# harp_behavior_encoder_v1_2.net
KiCad netlist of a schematic drawn in EAGLE
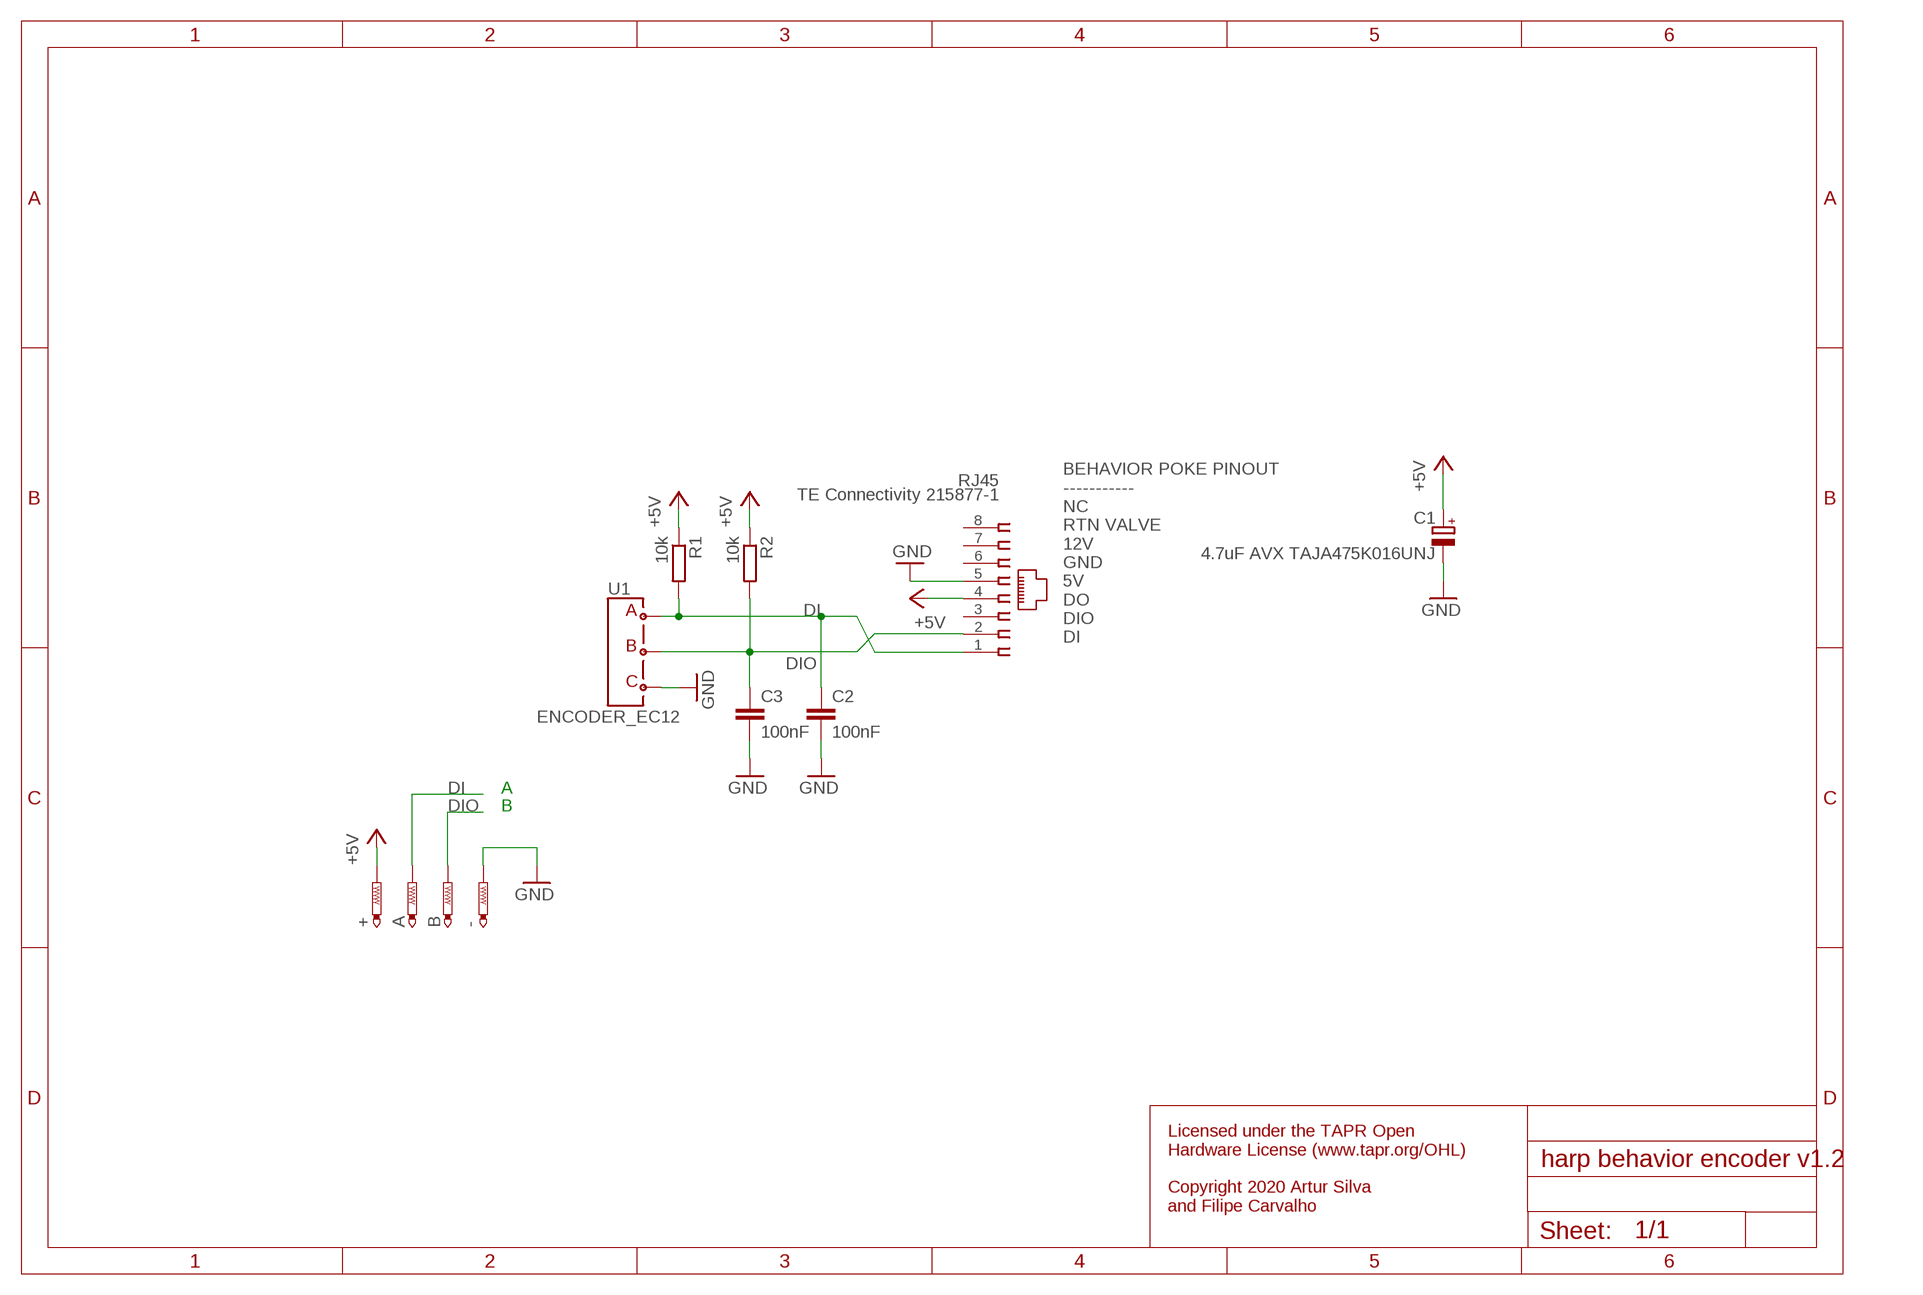
[diagram p0: schematic, sheet 1]

(export (version "E")
  (design (tool "Eeschema 10.0.6"))
  (components
    (comp (ref "+")
      (value "PTR1PAD1-13")
      (footprint "eagle-import:P1-13")
      (libsource (lib "eagle-import") (part "PTR1PAD1-13"))
    )
    (comp (ref "-")
      (value "PTR1PAD1-13")
      (footprint "eagle-import:P1-13")
      (libsource (lib "eagle-import") (part "PTR1PAD1-13"))
    )
    (comp (ref "A")
      (value "PTR1PAD1-13")
      (footprint "eagle-import:P1-13")
      (libsource (lib "eagle-import") (part "PTR1PAD1-13"))
    )
    (comp (ref "B")
      (value "PTR1PAD1-13")
      (footprint "eagle-import:P1-13")
      (libsource (lib "eagle-import") (part "PTR1PAD1-13"))
    )
    (comp (ref "C1")
      (value "4.7uF AVX TAJA475K016UNJ")
      (footprint "eagle-import:A_3216-18W")
      (libsource (lib "eagle-import") (part "CPOL-EUA/3216-18W"))
    )
    (comp (ref "C2")
      (value "100nF")
      (footprint "eagle-import:C0402")
      (libsource (lib "eagle-import") (part "C-EUC0402"))
    )
    (comp (ref "C3")
      (value "100nF")
      (footprint "eagle-import:C0402")
      (libsource (lib "eagle-import") (part "C-EUC0402"))
    )
    (comp (ref "R1")
      (value "10k")
      (footprint "eagle-import:R0402")
      (libsource (lib "eagle-import") (part "R-EU_R0402"))
    )
    (comp (ref "R2")
      (value "10k")
      (footprint "eagle-import:R0402")
      (libsource (lib "eagle-import") (part "R-EU_R0402"))
    )
    (comp (ref "RJ45")
      (value "TE Connectivity 215877-1")
      (footprint "eagle-import:520426-4")
      (libsource (lib "eagle-import") (part "520426-4"))
    )
    (comp (ref "U1")
      (value "ENCODER_EC12")
      (footprint "eagle-import:ENCODER_EC12")
      (libsource (lib "eagle-import") (part "ENCODER_EC12"))
    )
  )
  (nets
    (net (code "1") (name "+5V") (class "Default")
      (node (ref "+") (pin "TP") (pinfunction "TP_TP") (pintype "input"))
      (node (ref "C1") (pin "+") (pinfunction "+_+") (pintype "passive"))
      (node (ref "R1") (pin "1") (pinfunction "1_1") (pintype "passive"))
      (node (ref "R2") (pin "1") (pinfunction "1_1") (pintype "passive"))
      (node (ref "RJ45") (pin "4") (pinfunction "4_4") (pintype "passive"))
    )
    (net (code "2") (name "/DI") (class "Default")
      (node (ref "A") (pin "TP") (pinfunction "TP_TP") (pintype "input"))
      (node (ref "C2") (pin "1") (pinfunction "1_1") (pintype "passive"))
      (node (ref "R1") (pin "2") (pinfunction "2_2") (pintype "passive"))
      (node (ref "RJ45") (pin "1") (pinfunction "1_1") (pintype "passive"))
      (node (ref "U1") (pin "A") (pinfunction "A_A") (pintype "bidirectional"))
    )
    (net (code "3") (name "/DIO") (class "Default")
      (node (ref "B") (pin "TP") (pinfunction "TP_TP") (pintype "input"))
      (node (ref "C3") (pin "1") (pinfunction "1_1") (pintype "passive"))
      (node (ref "R2") (pin "2") (pinfunction "2_2") (pintype "passive"))
      (node (ref "RJ45") (pin "2") (pinfunction "2_2") (pintype "passive"))
      (node (ref "U1") (pin "B") (pinfunction "B_B") (pintype "bidirectional"))
    )
    (net (code "4") (name "GND") (class "Default")
      (node (ref "-") (pin "TP") (pinfunction "TP_TP") (pintype "input"))
      (node (ref "C1") (pin "-") (pinfunction "-_-") (pintype "passive"))
      (node (ref "C2") (pin "2") (pinfunction "2_2") (pintype "passive"))
      (node (ref "C3") (pin "2") (pinfunction "2_2") (pintype "passive"))
      (node (ref "RJ45") (pin "5") (pinfunction "5_5") (pintype "passive"))
      (node (ref "U1") (pin "C") (pinfunction "C_C") (pintype "bidirectional"))
    )
    (net (code "5") (name "unconnected-(RJ45-Pad3)") (class "Default")
      (node (ref "RJ45") (pin "3") (pinfunction "3_3") (pintype "passive"))
    )
    (net (code "6") (name "unconnected-(RJ45-Pad6)") (class "Default")
      (node (ref "RJ45") (pin "6") (pinfunction "6_6") (pintype "passive"))
    )
    (net (code "7") (name "unconnected-(RJ45-Pad7)") (class "Default")
      (node (ref "RJ45") (pin "7") (pinfunction "7_7") (pintype "passive"))
    )
    (net (code "8") (name "unconnected-(RJ45-Pad8)") (class "Default")
      (node (ref "RJ45") (pin "8") (pinfunction "8_8") (pintype "passive"))
    )
  )
)
